# mother_card_15.net
KiCad netlist of a schematic drawn in EAGLE
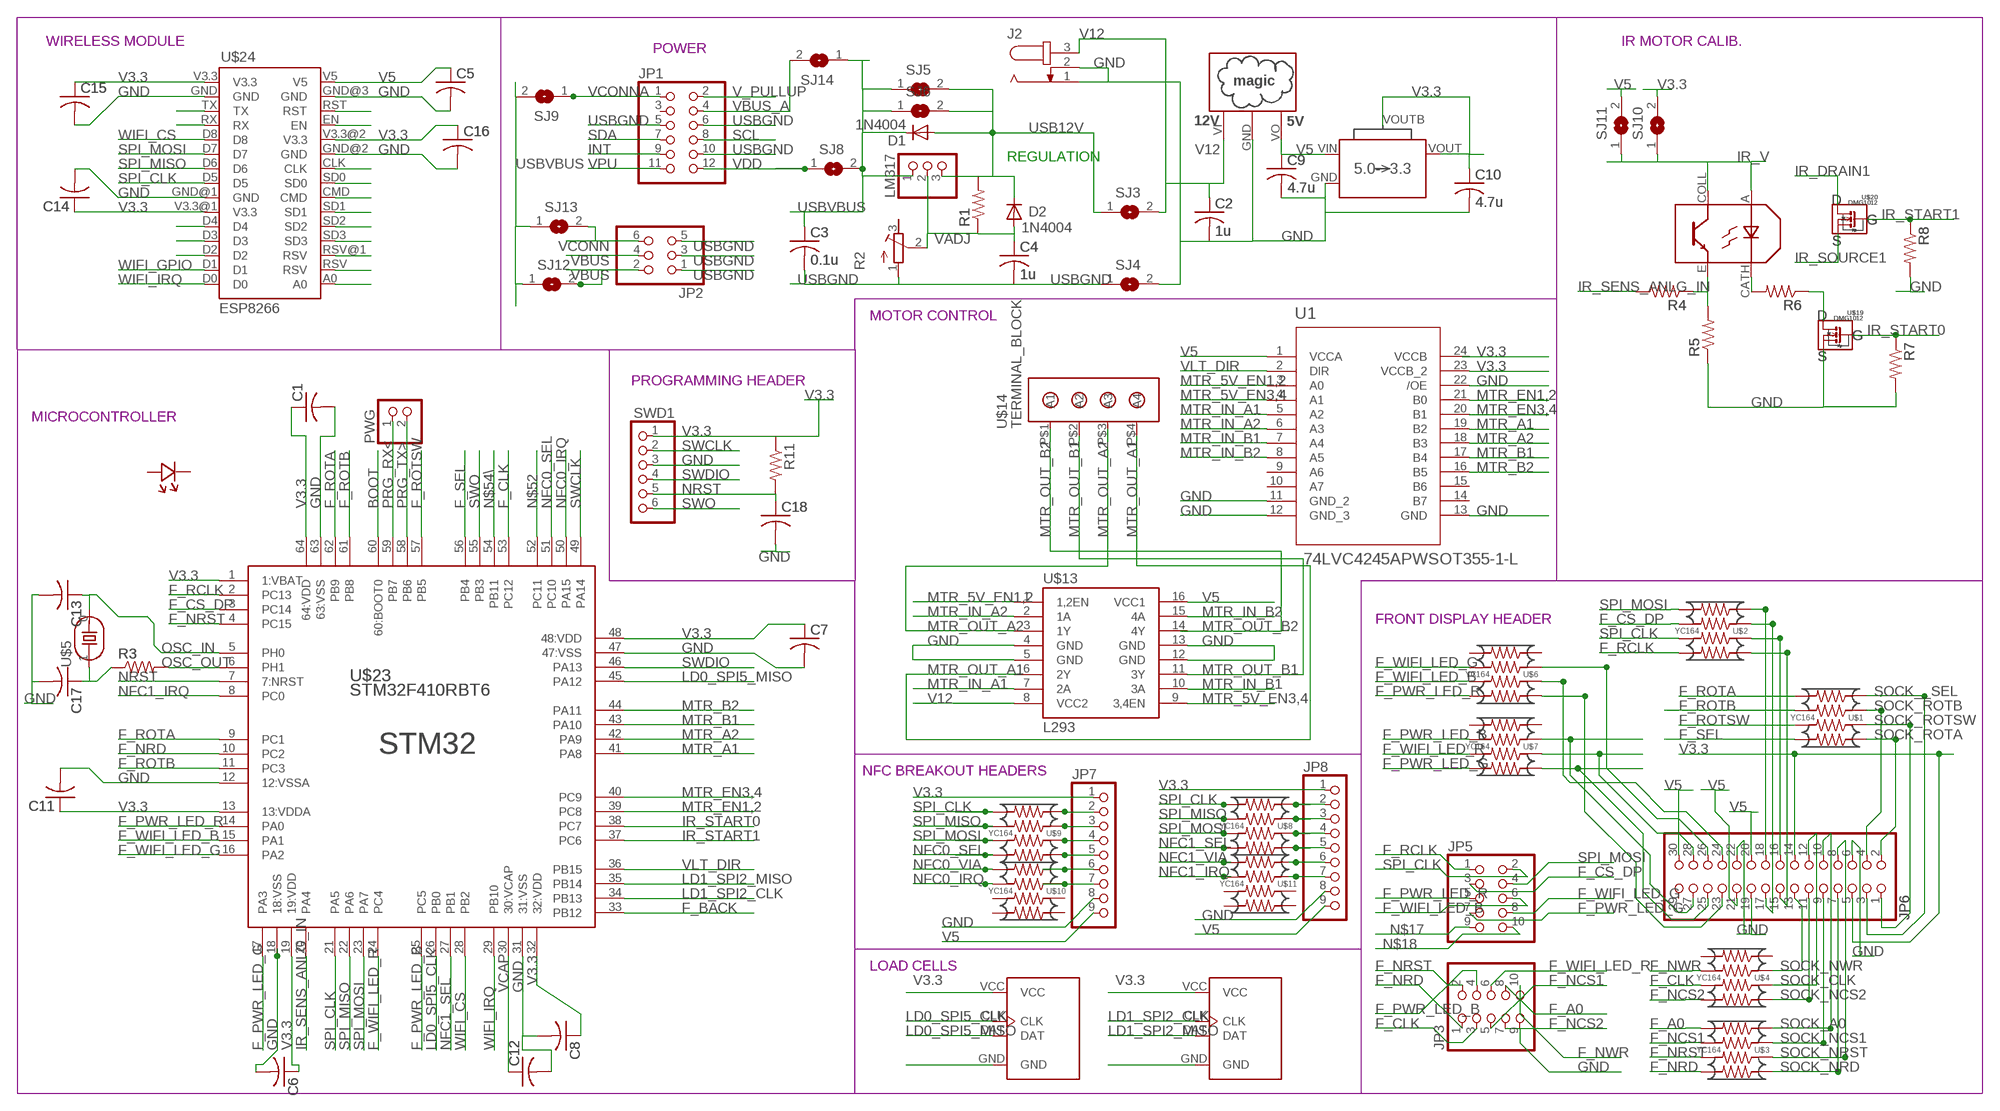
[diagram p0: schematic, sheet 1]

(export (version "E")
  (design (tool "Eeschema 10.0.6"))
  (components
    (comp (ref "C1")
      (value "C-USC0805")
      (footprint "eagle-import:C0805")
      (libsource (lib "eagle-import") (part "C-USC0805"))
    )
    (comp (ref "C2")
      (value "1u")
      (footprint "eagle-import:C0805")
      (libsource (lib "eagle-import") (part "C-USC0805"))
    )
    (comp (ref "C3")
      (value "0.1u")
      (footprint "eagle-import:C0805")
      (libsource (lib "eagle-import") (part "C-USC0805"))
    )
    (comp (ref "C4")
      (value "1u")
      (footprint "eagle-import:C0805")
      (libsource (lib "eagle-import") (part "C-USC0805"))
    )
    (comp (ref "C5")
      (value "C-USC0805")
      (footprint "eagle-import:C0805")
      (libsource (lib "eagle-import") (part "C-USC0805"))
    )
    (comp (ref "C6")
      (value "C-USC0805")
      (footprint "eagle-import:C0805")
      (libsource (lib "eagle-import") (part "C-USC0805"))
    )
    (comp (ref "C7")
      (value "C-USC0805")
      (footprint "eagle-import:C0805")
      (libsource (lib "eagle-import") (part "C-USC0805"))
    )
    (comp (ref "C8")
      (value "C-USC0805")
      (footprint "eagle-import:C0805")
      (libsource (lib "eagle-import") (part "C-USC0805"))
    )
    (comp (ref "C9")
      (value "4.7u")
      (footprint "eagle-import:C0805")
      (libsource (lib "eagle-import") (part "C-USC0805"))
    )
    (comp (ref "C10")
      (value "4.7u")
      (footprint "eagle-import:C0805")
      (libsource (lib "eagle-import") (part "C-USC0805"))
    )
    (comp (ref "C11")
      (value "C-USC0805")
      (footprint "eagle-import:C0805")
      (libsource (lib "eagle-import") (part "C-USC0805"))
    )
    (comp (ref "C12")
      (value "C-USC0805")
      (footprint "eagle-import:C0805")
      (libsource (lib "eagle-import") (part "C-USC0805"))
    )
    (comp (ref "C13")
      (value "C-USC0603")
      (footprint "eagle-import:C0603")
      (libsource (lib "eagle-import") (part "C-USC0603"))
    )
    (comp (ref "C14")
      (value "C-USC0805")
      (footprint "eagle-import:C0805")
      (libsource (lib "eagle-import") (part "C-USC0805"))
    )
    (comp (ref "C15")
      (value "C-USC0805")
      (footprint "eagle-import:C0805")
      (libsource (lib "eagle-import") (part "C-USC0805"))
    )
    (comp (ref "C16")
      (value "C-USC0805")
      (footprint "eagle-import:C0805")
      (libsource (lib "eagle-import") (part "C-USC0805"))
    )
    (comp (ref "C17")
      (value "C-USC0603")
      (footprint "eagle-import:C0603")
      (libsource (lib "eagle-import") (part "C-USC0603"))
    )
    (comp (ref "C18")
      (value "C-USC0805")
      (footprint "eagle-import:C0805")
      (libsource (lib "eagle-import") (part "C-USC0805"))
    )
    (comp (ref "D1")
      (value "1N4004")
      (footprint "eagle-import:DO41-10")
      (libsource (lib "eagle-import") (part "1N4004"))
    )
    (comp (ref "D2")
      (value "1N4004")
      (footprint "eagle-import:DO41-10")
      (libsource (lib "eagle-import") (part "1N4004"))
    )
    (comp (ref "J2")
      (value "JACK-PLUG0")
      (footprint "eagle-import:SPC4077")
      (libsource (lib "eagle-import") (part "JACK-PLUG0"))
    )
    (comp (ref "JP1")
      (value "PINHD-2X6")
      (footprint "eagle-import:2X06")
      (libsource (lib "eagle-import") (part "PINHD-2X6"))
    )
    (comp (ref "JP2")
      (value "PINHD-2X3")
      (footprint "eagle-import:2X03")
      (libsource (lib "eagle-import") (part "PINHD-2X3"))
    )
    (comp (ref "JP3")
      (value "PINHD-2X5")
      (footprint "eagle-import:2X05")
      (libsource (lib "eagle-import") (part "PINHD-2X5"))
    )
    (comp (ref "JP5")
      (value "PINHD-2X5")
      (footprint "eagle-import:2X05")
      (libsource (lib "eagle-import") (part "PINHD-2X5"))
    )
    (comp (ref "JP6")
      (value "PINHD-2X15/SOCK")
      (footprint "eagle-import:2X15_SOCK")
      (libsource (lib "eagle-import") (part "PINHD-2X15/SOCK"))
    )
    (comp (ref "JP7")
      (value "PINHD-1X9/90")
      (footprint "eagle-import:1X09_90")
      (libsource (lib "eagle-import") (part "PINHD-1X9/90"))
    )
    (comp (ref "JP8")
      (value "PINHD-1X9/90")
      (footprint "eagle-import:1X09_90")
      (libsource (lib "eagle-import") (part "PINHD-1X9/90"))
    )
    (comp (ref "LM317")
      (value "PINHD-1X3")
      (footprint "eagle-import:1X03")
      (libsource (lib "eagle-import") (part "PINHD-1X3"))
    )
    (comp (ref "PWG")
      (value "PINHD-1X2")
      (footprint "eagle-import:1X02")
      (libsource (lib "eagle-import") (part "PINHD-1X2"))
    )
    (comp (ref "R1")
      (value "R-US_R0805")
      (footprint "eagle-import:R0805")
      (libsource (lib "eagle-import") (part "seniorDesign_R-US_R0805"))
    )
    (comp (ref "R2")
      (value "R-TRIMM64W")
      (footprint "eagle-import:RTRIM64W")
      (libsource (lib "eagle-import") (part "R-TRIMM64W"))
    )
    (comp (ref "R3")
      (value "R-US_R0805")
      (footprint "eagle-import:R0805")
      (libsource (lib "eagle-import") (part "seniorDesign_R-US_R0805"))
    )
    (comp (ref "R4")
      (value "R-US_R0805")
      (footprint "eagle-import:R0805")
      (libsource (lib "eagle-import") (part "seniorDesign_R-US_R0805"))
    )
    (comp (ref "R5")
      (value "R-US_R0805")
      (footprint "eagle-import:R0805")
      (libsource (lib "eagle-import") (part "seniorDesign_R-US_R0805"))
    )
    (comp (ref "R6")
      (value "R-US_R0805")
      (footprint "eagle-import:R0805")
      (libsource (lib "eagle-import") (part "seniorDesign_R-US_R0805"))
    )
    (comp (ref "R7")
      (value "R-US_R0805")
      (footprint "eagle-import:R0805")
      (libsource (lib "eagle-import") (part "seniorDesign_R-US_R0805"))
    )
    (comp (ref "R8")
      (value "R-US_R0805")
      (footprint "eagle-import:R0805")
      (libsource (lib "eagle-import") (part "seniorDesign_R-US_R0805"))
    )
    (comp (ref "R11")
      (value "R-US_R0805")
      (footprint "eagle-import:R0805")
      (libsource (lib "eagle-import") (part "R-US_R0805"))
    )
    (comp (ref "SJ3") (value "SJ") (footprint "eagle-import:SJ") (libsource (lib "eagle-import") (part "SJ")))
    (comp (ref "SJ4") (value "SJ") (footprint "eagle-import:SJ") (libsource (lib "eagle-import") (part "SJ")))
    (comp (ref "SJ5") (value "SJ") (footprint "eagle-import:SJ") (libsource (lib "eagle-import") (part "SJ")))
    (comp (ref "SJ6") (value "SJ") (footprint "eagle-import:SJ") (libsource (lib "eagle-import") (part "SJ")))
    (comp (ref "SJ8") (value "SJ") (footprint "eagle-import:SJ") (libsource (lib "eagle-import") (part "SJ")))
    (comp (ref "SJ9") (value "SJ") (footprint "eagle-import:SJ") (libsource (lib "eagle-import") (part "SJ")))
    (comp (ref "SJ10")
      (value "SJ")
      (footprint "eagle-import:SJ")
      (libsource (lib "eagle-import") (part "SJ"))
    )
    (comp (ref "SJ11")
      (value "SJ")
      (footprint "eagle-import:SJ")
      (libsource (lib "eagle-import") (part "SJ"))
    )
    (comp (ref "SJ12")
      (value "SJ")
      (footprint "eagle-import:SJ")
      (libsource (lib "eagle-import") (part "SJ"))
    )
    (comp (ref "SJ13")
      (value "SJ")
      (footprint "eagle-import:SJ")
      (libsource (lib "eagle-import") (part "SJ"))
    )
    (comp (ref "SJ14")
      (value "SJ")
      (footprint "eagle-import:SJ")
      (libsource (lib "eagle-import") (part "SJ"))
    )
    (comp (ref "SWD1")
      (value "PINHD-1X6")
      (footprint "eagle-import:1X06")
      (libsource (lib "eagle-import") (part "PINHD-1X6"))
    )
    (comp (ref "U$1")
      (value "YC164")
      (footprint "eagle-import:YC164")
      (libsource (lib "eagle-import") (part "YC164"))
    )
    (comp (ref "U$2")
      (value "YC164")
      (footprint "eagle-import:YC164")
      (libsource (lib "eagle-import") (part "YC164"))
    )
    (comp (ref "U$3")
      (value "YC164")
      (footprint "eagle-import:YC164")
      (libsource (lib "eagle-import") (part "YC164"))
    )
    (comp (ref "U$4")
      (value "YC164")
      (footprint "eagle-import:YC164")
      (libsource (lib "eagle-import") (part "YC164"))
    )
    (comp (ref "U$5")
      (value "HC-49S_9B")
      (footprint "eagle-import:HC-49S_9B")
      (libsource (lib "eagle-import") (part "HC-49S_9B"))
    )
    (comp (ref "U$6")
      (value "YC164")
      (footprint "eagle-import:YC164")
      (libsource (lib "eagle-import") (part "YC164"))
    )
    (comp (ref "U$7")
      (value "YC164")
      (footprint "eagle-import:YC164")
      (libsource (lib "eagle-import") (part "YC164"))
    )
    (comp (ref "U$8")
      (value "YC164")
      (footprint "eagle-import:YC164")
      (libsource (lib "eagle-import") (part "YC164"))
    )
    (comp (ref "U$9")
      (value "YC164")
      (footprint "eagle-import:YC164")
      (libsource (lib "eagle-import") (part "YC164"))
    )
    (comp (ref "U$10")
      (value "YC164")
      (footprint "eagle-import:YC164")
      (libsource (lib "eagle-import") (part "YC164"))
    )
    (comp (ref "U$11")
      (value "YC164")
      (footprint "eagle-import:YC164")
      (libsource (lib "eagle-import") (part "YC164"))
    )
    (comp (ref "U$12")
      (value "LED0603")
      (footprint "eagle-import:LED")
      (libsource (lib "eagle-import") (part "LED0603"))
    )
    (comp (ref "U$13")
      (value "L293")
      (footprint "eagle-import:DIL16")
      (libsource (lib "eagle-import") (part "L293"))
    )
    (comp (ref "U$14")
      (value "TERMINAL_BLOCK")
      (footprint "eagle-import:1X4_BLOCK")
      (libsource (lib "eagle-import") (part "TERMINAL_BLOCK"))
    )
    (comp (ref "U$15")
      (value "AP2114H")
      (footprint "eagle-import:AP2114H")
      (libsource (lib "eagle-import") (part "AP2114H"))
    )
    (comp (ref "U$16")
      (value "OKI-78SR-W36")
      (footprint "eagle-import:SIP3")
      (libsource (lib "eagle-import") (part "OKI-78SR-W36"))
    )
    (comp (ref "U$18")
      (value "TCRT5000")
      (footprint "eagle-import:TCRT5000")
      (libsource (lib "eagle-import") (part "TCRT5000"))
    )
    (comp (ref "U$19")
      (value "DMG1012")
      (footprint "eagle-import:SOT323")
      (libsource (lib "eagle-import") (part "DMG1012"))
    )
    (comp (ref "U$20")
      (value "DMG1012")
      (footprint "eagle-import:SOT323")
      (libsource (lib "eagle-import") (part "DMG1012"))
    )
    (comp (ref "U$21")
      (value "HX711")
      (footprint "eagle-import:HX711")
      (libsource (lib "eagle-import") (part "HX711"))
    )
    (comp (ref "U$22")
      (value "HX711")
      (footprint "eagle-import:HX711")
      (libsource (lib "eagle-import") (part "HX711"))
    )
    (comp (ref "U$23")
      (value "STM32F410RBT6")
      (footprint "eagle-import:QFP50P1200X1200X160-64N")
      (libsource (lib "eagle-import") (part "STM32F410RBT6"))
    )
    (comp (ref "U$24")
      (value "ESP8266")
      (footprint "eagle-import:ESP8266")
      (libsource (lib "eagle-import") (part "ESP8266"))
    )
    (comp (ref "U1")
      (value "74LVC4245APWSOT355-1-L")
      (footprint "eagle-import:SOT355-1-L")
      (fields (field (name "MANUFACTURER_PART_NUMBER") "74LVC4245APW"))
      (libsource (lib "eagle-import") (part "74LVC4245APWSOT355-1-L"))
    )
  )
  (nets
    (net (code "1") (name "/BOOT") (class "Default")
      (node (ref "U$23") (pin "60") (pinfunction "60:BOOT0_60") (pintype "bidirectional"))
    )
    (net (code "2") (name "/F_A0") (class "Default")
      (node (ref "JP3") (pin "8") (pinfunction "8_8") (pintype "passive"))
      (node (ref "U$3") (pin "P$4") (pinfunction "4_P$4") (pintype "passive"))
    )
    (net (code "3") (name "/F_BACK") (class "Default")
      (node (ref "U$23") (pin "33") (pinfunction "PB12_33") (pintype "bidirectional"))
    )
    (net (code "4") (name "/F_CLK") (class "Default")
      (node (ref "JP3") (pin "3") (pinfunction "3_3") (pintype "passive"))
      (node (ref "U$23") (pin "53") (pinfunction "PC12_53") (pintype "bidirectional"))
      (node (ref "U$4") (pin "P$2") (pinfunction "2_P$2") (pintype "passive"))
    )
    (net (code "5") (name "/F_CS_DP") (class "Default")
      (node (ref "JP5") (pin "3") (pinfunction "3_3") (pintype "passive"))
      (node (ref "U$2") (pin "P$3") (pinfunction "3_P$3") (pintype "passive"))
      (node (ref "U$23") (pin "3") (pinfunction "PC14_3") (pintype "bidirectional"))
    )
    (net (code "6") (name "/F_NCS1") (class "Default")
      (node (ref "JP3") (pin "5") (pinfunction "5_5") (pintype "passive"))
      (node (ref "U$3") (pin "P$3") (pinfunction "3_P$3") (pintype "passive"))
    )
    (net (code "7") (name "/F_NCS2") (class "Default")
      (node (ref "JP3") (pin "7") (pinfunction "7_7") (pintype "passive"))
      (node (ref "U$4") (pin "P$1") (pinfunction "1_P$1") (pintype "passive"))
    )
    (net (code "8") (name "/F_NRD") (class "Default")
      (node (ref "JP3") (pin "1") (pinfunction "1_1") (pintype "passive"))
      (node (ref "U$23") (pin "10") (pinfunction "PC2_10") (pintype "bidirectional"))
      (node (ref "U$3") (pin "P$1") (pinfunction "1_P$1") (pintype "passive"))
    )
    (net (code "9") (name "/F_NRST") (class "Default")
      (node (ref "JP3") (pin "2") (pinfunction "2_2") (pintype "passive"))
      (node (ref "U$23") (pin "4") (pinfunction "PC15_4") (pintype "bidirectional"))
      (node (ref "U$3") (pin "P$2") (pinfunction "2_P$2") (pintype "passive"))
    )
    (net (code "10") (name "/F_NWR") (class "Default")
      (node (ref "JP3") (pin "10") (pinfunction "10_10") (pintype "passive"))
      (node (ref "U$4") (pin "P$3") (pinfunction "3_P$3") (pintype "passive"))
    )
    (net (code "11") (name "/F_PWR_LED_B") (class "Default")
      (node (ref "JP3") (pin "4") (pinfunction "4_4") (pintype "passive"))
      (node (ref "U$23") (pin "25") (pinfunction "PC5_25") (pintype "bidirectional"))
      (node (ref "U$7") (pin "P$3") (pinfunction "3_P$3") (pintype "passive"))
    )
    (net (code "12") (name "/F_PWR_LED_G") (class "Default")
      (node (ref "JP5") (pin "7") (pinfunction "7_7") (pintype "passive"))
      (node (ref "U$23") (pin "17") (pinfunction "PA3_17") (pintype "bidirectional"))
      (node (ref "U$7") (pin "P$1") (pinfunction "1_P$1") (pintype "passive"))
    )
    (net (code "13") (name "/F_PWR_LED_R") (class "Default")
      (node (ref "JP5") (pin "5") (pinfunction "5_5") (pintype "passive"))
      (node (ref "U$23") (pin "14") (pinfunction "PA0_14") (pintype "bidirectional"))
      (node (ref "U$6") (pin "P$1") (pinfunction "1_P$1") (pintype "passive"))
    )
    (net (code "14") (name "/F_RCLK") (class "Default")
      (node (ref "JP5") (pin "1") (pinfunction "1_1") (pintype "passive"))
      (node (ref "U$2") (pin "P$1") (pinfunction "1_P$1") (pintype "passive"))
      (node (ref "U$23") (pin "2") (pinfunction "PC13_2") (pintype "bidirectional"))
    )
    (net (code "15") (name "/F_ROTA") (class "Default")
      (node (ref "U$1") (pin "P$4") (pinfunction "4_P$4") (pintype "passive"))
      (node (ref "U$23") (pin "62") (pinfunction "PB9_62") (pintype "bidirectional"))
      (node (ref "U$23") (pin "9") (pinfunction "PC1_9") (pintype "bidirectional"))
    )
    (net (code "16") (name "/F_ROTB") (class "Default")
      (node (ref "U$1") (pin "P$3") (pinfunction "3_P$3") (pintype "passive"))
      (node (ref "U$23") (pin "11") (pinfunction "PC3_11") (pintype "bidirectional"))
      (node (ref "U$23") (pin "61") (pinfunction "PB8_61") (pintype "bidirectional"))
    )
    (net (code "17") (name "/F_ROTSW") (class "Default")
      (node (ref "U$1") (pin "P$2") (pinfunction "2_P$2") (pintype "passive"))
      (node (ref "U$23") (pin "57") (pinfunction "PB5_57") (pintype "bidirectional"))
    )
    (net (code "18") (name "/F_SEL") (class "Default")
      (node (ref "U$1") (pin "P$1") (pinfunction "1_P$1") (pintype "passive"))
      (node (ref "U$23") (pin "56") (pinfunction "PB4_56") (pintype "bidirectional"))
    )
    (net (code "19") (name "/F_WIFI_LED_B") (class "Default")
      (node (ref "JP5") (pin "6") (pinfunction "6_6") (pintype "passive"))
      (node (ref "U$23") (pin "15") (pinfunction "PA1_15") (pintype "bidirectional"))
      (node (ref "U$6") (pin "P$2") (pinfunction "2_P$2") (pintype "passive"))
    )
    (net (code "20") (name "/F_WIFI_LED_G") (class "Default")
      (node (ref "JP5") (pin "8") (pinfunction "8_8") (pintype "passive"))
      (node (ref "U$23") (pin "16") (pinfunction "PA2_16") (pintype "bidirectional"))
      (node (ref "U$6") (pin "P$3") (pinfunction "3_P$3") (pintype "passive"))
    )
    (net (code "21") (name "/F_WIFI_LED_R") (class "Default")
      (node (ref "JP3") (pin "6") (pinfunction "6_6") (pintype "passive"))
      (node (ref "U$23") (pin "24") (pinfunction "PC4_24") (pintype "bidirectional"))
      (node (ref "U$7") (pin "P$2") (pinfunction "2_P$2") (pintype "passive"))
    )
    (net (code "22") (name "/GND") (class "Default")
      (node (ref "C1") (pin "2") (pinfunction "2_2") (pintype "passive"))
      (node (ref "C10") (pin "2") (pinfunction "2_2") (pintype "passive"))
      (node (ref "C11") (pin "2") (pinfunction "2_2") (pintype "passive"))
      (node (ref "C12") (pin "2") (pinfunction "2_2") (pintype "passive"))
      (node (ref "C13") (pin "2") (pinfunction "2_2") (pintype "passive"))
      (node (ref "C14") (pin "2") (pinfunction "2_2") (pintype "passive"))
      (node (ref "C15") (pin "2") (pinfunction "2_2") (pintype "passive"))
      (node (ref "C16") (pin "2") (pinfunction "2_2") (pintype "passive"))
      (node (ref "C17") (pin "2") (pinfunction "2_2") (pintype "passive"))
      (node (ref "C18") (pin "2") (pinfunction "2_2") (pintype "passive"))
      (node (ref "C2") (pin "2") (pinfunction "2_2") (pintype "passive"))
      (node (ref "C5") (pin "2") (pinfunction "2_2") (pintype "passive"))
      (node (ref "C6") (pin "2") (pinfunction "2_2") (pintype "passive"))
      (node (ref "C7") (pin "2") (pinfunction "2_2") (pintype "passive"))
      (node (ref "C8") (pin "2") (pinfunction "2_2") (pintype "passive"))
      (node (ref "C9") (pin "2") (pinfunction "2_2") (pintype "passive"))
      (node (ref "J2") (pin "1") (pinfunction "1_1") (pintype "passive"))
      (node (ref "J2") (pin "2") (pinfunction "2_2") (pintype "passive"))
      (node (ref "JP3") (pin "9") (pinfunction "9_9") (pintype "passive"))
      (node (ref "JP6") (pin "19") (pinfunction "19_19") (pintype "passive"))
      (node (ref "JP6") (pin "22") (pinfunction "22_22") (pintype "passive"))
      (node (ref "JP6") (pin "6") (pinfunction "6_6") (pintype "passive"))
      (node (ref "JP7") (pin "8") (pinfunction "8_8") (pintype "passive"))
      (node (ref "JP8") (pin "8") (pinfunction "8_8") (pintype "passive"))
      (node (ref "R5") (pin "1") (pinfunction "1_1") (pintype "passive"))
      (node (ref "R7") (pin "2") (pinfunction "2_2") (pintype "passive"))
      (node (ref "R8") (pin "2") (pinfunction "2_2") (pintype "passive"))
      (node (ref "SJ4") (pin "2") (pinfunction "2_2") (pintype "passive"))
      (node (ref "SWD1") (pin "3") (pinfunction "3_3") (pintype "passive"))
      (node (ref "U$13") (pin "12") (pinfunction "GND_12") (pintype "bidirectional"))
      (node (ref "U$13") (pin "13") (pinfunction "GND_13") (pintype "bidirectional"))
      (node (ref "U$13") (pin "4") (pinfunction "GND_4") (pintype "bidirectional"))
      (node (ref "U$13") (pin "5") (pinfunction "GND_5") (pintype "bidirectional"))
      (node (ref "U$15") (pin "GND") (pinfunction "GND_GND") (pintype "power_in"))
      (node (ref "U$16") (pin "GND") (pinfunction "P$2_GND") (pintype "power_in"))
      (node (ref "U$19") (pin "S") (pinfunction "S_S") (pintype "bidirectional"))
      (node (ref "U$21") (pin "GND") (pinfunction "GND_GND") (pintype "power_in"))
      (node (ref "U$22") (pin "GND") (pinfunction "GND_GND") (pintype "power_in"))
      (node (ref "U$23") (pin "12") (pinfunction "12:VSSA_12") (pintype "bidirectional"))
      (node (ref "U$23") (pin "18") (pinfunction "18:VSS_18") (pintype "bidirectional"))
      (node (ref "U$23") (pin "31") (pinfunction "31:VSS_31") (pintype "bidirectional"))
      (node (ref "U$23") (pin "47") (pinfunction "47:VSS_47") (pintype "bidirectional"))
      (node (ref "U$23") (pin "63") (pinfunction "63:VSS_63") (pintype "bidirectional"))
      (node (ref "U$24") (pin "GND") (pinfunction "GND_GND") (pintype "bidirectional"))
      (node (ref "U$24") (pin "GND@1") (pinfunction "GND_GND@1") (pintype "bidirectional"))
      (node (ref "U$24") (pin "GND@2") (pinfunction "GND_GND@2") (pintype "bidirectional"))
      (node (ref "U$24") (pin "GND@3") (pinfunction "GND_GND@3") (pintype "bidirectional"))
      (node (ref "U1") (pin "11") (pinfunction "GND_2_11") (pintype "power_in"))
      (node (ref "U1") (pin "12") (pinfunction "GND_3_12") (pintype "power_in"))
      (node (ref "U1") (pin "13") (pinfunction "GND_13") (pintype "power_in"))
      (node (ref "U1") (pin "22") (pinfunction "/OE_22") (pintype "input"))
    )
    (net (code "23") (name "/INT") (class "Default")
      (node (ref "JP1") (pin "9") (pinfunction "9_9") (pintype "passive"))
    )
    (net (code "24") (name "/IR_DRAIN1") (class "Default")
      (node (ref "U$20") (pin "D") (pinfunction "D_D") (pintype "bidirectional"))
    )
    (net (code "25") (name "/IR_SENS_ANLG_IN") (class "Default")
      (node (ref "R4") (pin "2") (pinfunction "2_2") (pintype "passive"))
      (node (ref "U$23") (pin "20") (pinfunction "PA4_20") (pintype "bidirectional"))
    )
    (net (code "26") (name "/IR_SOURCE1") (class "Default")
      (node (ref "U$20") (pin "S") (pinfunction "S_S") (pintype "bidirectional"))
    )
    (net (code "27") (name "/IR_START0") (class "Default")
      (node (ref "R7") (pin "1") (pinfunction "1_1") (pintype "passive"))
      (node (ref "U$19") (pin "G") (pinfunction "G_G") (pintype "bidirectional"))
      (node (ref "U$23") (pin "38") (pinfunction "PC7_38") (pintype "bidirectional"))
    )
    (net (code "28") (name "/IR_START1") (class "Default")
      (node (ref "R8") (pin "1") (pinfunction "1_1") (pintype "passive"))
      (node (ref "U$20") (pin "G") (pinfunction "G_G") (pintype "bidirectional"))
      (node (ref "U$23") (pin "37") (pinfunction "PC6_37") (pintype "bidirectional"))
    )
    (net (code "29") (name "/IR_V") (class "Default")
      (node (ref "SJ10") (pin "1") (pinfunction "1_1") (pintype "passive"))
      (node (ref "SJ11") (pin "1") (pinfunction "1_1") (pintype "passive"))
      (node (ref "U$18") (pin "A") (pinfunction "A_A") (pintype "bidirectional"))
      (node (ref "U$18") (pin "COLL") (pinfunction "COLL_COLL") (pintype "bidirectional"))
    )
    (net (code "30") (name "/LD0_SPI5_CLK") (class "Default")
      (node (ref "U$21") (pin "CLK") (pinfunction "CLK_CLK") (pintype "bidirectional"))
      (node (ref "U$23") (pin "26") (pinfunction "PB0_26") (pintype "bidirectional"))
    )
    (net (code "31") (name "/LD0_SPI5_MISO") (class "Default")
      (node (ref "U$21") (pin "DAT") (pinfunction "DAT_DAT") (pintype "bidirectional"))
      (node (ref "U$23") (pin "45") (pinfunction "PA12_45") (pintype "bidirectional"))
    )
    (net (code "32") (name "/LD1_SPI2_CLK") (class "Default")
      (node (ref "U$22") (pin "CLK") (pinfunction "CLK_CLK") (pintype "bidirectional"))
      (node (ref "U$23") (pin "34") (pinfunction "PB13_34") (pintype "bidirectional"))
    )
    (net (code "33") (name "/LD1_SPI2_MISO") (class "Default")
      (node (ref "U$22") (pin "DAT") (pinfunction "DAT_DAT") (pintype "bidirectional"))
      (node (ref "U$23") (pin "35") (pinfunction "PB14_35") (pintype "bidirectional"))
    )
    (net (code "34") (name "/MTR_5V_EN1,2") (class "Default")
      (node (ref "U$13") (pin "1") (pinfunction "1,2EN_1") (pintype "bidirectional"))
      (node (ref "U1") (pin "3") (pinfunction "A0_3") (pintype "bidirectional"))
    )
    (net (code "35") (name "/MTR_5V_EN3,4") (class "Default")
      (node (ref "U$13") (pin "9") (pinfunction "3,4EN_9") (pintype "bidirectional"))
      (node (ref "U1") (pin "4") (pinfunction "A1_4") (pintype "bidirectional"))
    )
    (net (code "36") (name "/MTR_A1") (class "Default")
      (node (ref "U$23") (pin "41") (pinfunction "PA8_41") (pintype "bidirectional"))
      (node (ref "U1") (pin "19") (pinfunction "B2_19") (pintype "bidirectional"))
    )
    (net (code "37") (name "/MTR_A2") (class "Default")
      (node (ref "U$23") (pin "42") (pinfunction "PA9_42") (pintype "bidirectional"))
      (node (ref "U1") (pin "18") (pinfunction "B3_18") (pintype "bidirectional"))
    )
    (net (code "38") (name "/MTR_B1") (class "Default")
      (node (ref "U$23") (pin "43") (pinfunction "PA10_43") (pintype "bidirectional"))
      (node (ref "U1") (pin "17") (pinfunction "B4_17") (pintype "bidirectional"))
    )
    (net (code "39") (name "/MTR_B2") (class "Default")
      (node (ref "U$23") (pin "44") (pinfunction "PA11_44") (pintype "bidirectional"))
      (node (ref "U1") (pin "16") (pinfunction "B5_16") (pintype "bidirectional"))
    )
    (net (code "40") (name "/MTR_EN1,2") (class "Default")
      (node (ref "U$23") (pin "39") (pinfunction "PC8_39") (pintype "bidirectional"))
      (node (ref "U1") (pin "21") (pinfunction "B0_21") (pintype "bidirectional"))
    )
    (net (code "41") (name "/MTR_EN3,4") (class "Default")
      (node (ref "U$23") (pin "40") (pinfunction "PC9_40") (pintype "bidirectional"))
      (node (ref "U1") (pin "20") (pinfunction "B1_20") (pintype "bidirectional"))
    )
    (net (code "42") (name "/MTR_IN_A1") (class "Default")
      (node (ref "U$13") (pin "7") (pinfunction "2A_7") (pintype "bidirectional"))
      (node (ref "U1") (pin "5") (pinfunction "A2_5") (pintype "bidirectional"))
    )
    (net (code "43") (name "/MTR_IN_A2") (class "Default")
      (node (ref "U$13") (pin "2") (pinfunction "1A_2") (pintype "bidirectional"))
      (node (ref "U1") (pin "6") (pinfunction "A3_6") (pintype "bidirectional"))
    )
    (net (code "44") (name "/MTR_IN_B1") (class "Default")
      (node (ref "U$13") (pin "10") (pinfunction "3A_10") (pintype "bidirectional"))
      (node (ref "U1") (pin "7") (pinfunction "A4_7") (pintype "bidirectional"))
    )
    (net (code "45") (name "/MTR_IN_B2") (class "Default")
      (node (ref "U$13") (pin "15") (pinfunction "4A_15") (pintype "bidirectional"))
      (node (ref "U1") (pin "8") (pinfunction "A5_8") (pintype "bidirectional"))
    )
    (net (code "46") (name "/MTR_OUT_A1") (class "Default")
      (node (ref "U$13") (pin "6") (pinfunction "2Y_6") (pintype "bidirectional"))
      (node (ref "U$14") (pin "P$4") (pinfunction "A4_P$4") (pintype "bidirectional"))
    )
    (net (code "47") (name "/MTR_OUT_A2") (class "Default")
      (node (ref "U$13") (pin "3") (pinfunction "1Y_3") (pintype "bidirectional"))
      (node (ref "U$14") (pin "P$3") (pinfunction "A3_P$3") (pintype "bidirectional"))
    )
    (net (code "48") (name "/MTR_OUT_B1") (class "Default")
      (node (ref "U$13") (pin "11") (pinfunction "3Y_11") (pintype "bidirectional"))
      (node (ref "U$14") (pin "P$2") (pinfunction "A2_P$2") (pintype "bidirectional"))
    )
    (net (code "49") (name "/MTR_OUT_B2") (class "Default")
      (node (ref "U$13") (pin "14") (pinfunction "4Y_14") (pintype "bidirectional"))
      (node (ref "U$14") (pin "P$1") (pinfunction "A1_P$1") (pintype "bidirectional"))
    )
    (net (code "50") (name "/N$17") (class "Default")
      (node (ref "JP5") (pin "9") (pinfunction "9_9") (pintype "passive"))
    )
    (net (code "51") (name "/N$18") (class "Default")
      (node (ref "JP5") (pin "10") (pinfunction "10_10") (pintype "passive"))
    )
    (net (code "52") (name "/N$52") (class "Default")
      (node (ref "U$23") (pin "52") (pinfunction "PC11_52") (pintype "bidirectional"))
    )
    (net (code "53") (name "/N$54\\") (class "Default")
      (node (ref "U$23") (pin "54") (pinfunction "PB11_54") (pintype "bidirectional"))
    )
    (net (code "54") (name "/NFC0_IRQ") (class "Default")
      (node (ref "U$10") (pin "P$3") (pinfunction "3_P$3") (pintype "passive"))
      (node (ref "U$23") (pin "50") (pinfunction "PA15_50") (pintype "bidirectional"))
    )
    (net (code "55") (name "/NFC0_SEL") (class "Default")
      (node (ref "U$23") (pin "51") (pinfunction "PC10_51") (pintype "bidirectional"))
      (node (ref "U$9") (pin "P$1") (pinfunction "1_P$1") (pintype "passive"))
    )
    (net (code "56") (name "/NFC0_VIA") (class "Default")
      (node (ref "U$10") (pin "P$4") (pinfunction "4_P$4") (pintype "passive"))
    )
    (net (code "57") (name "/NFC1_IRQ") (class "Default")
      (node (ref "U$11") (pin "P$3") (pinfunction "3_P$3") (pintype "passive"))
      (node (ref "U$23") (pin "8") (pinfunction "PC0_8") (pintype "bidirectional"))
    )
    (net (code "58") (name "/NFC1_SEL") (class "Default")
      (node (ref "U$23") (pin "27") (pinfunction "PB1_27") (pintype "bidirectional"))
      (node (ref "U$8") (pin "P$1") (pinfunction "1_P$1") (pintype "passive"))
    )
    (net (code "59") (name "/NFC1_VIA") (class "Default")
      (node (ref "U$11") (pin "P$4") (pinfunction "4_P$4") (pintype "passive"))
    )
    (net (code "60") (name "/NRST") (class "Default")
      (node (ref "C18") (pin "1") (pinfunction "1_1") (pintype "passive"))
      (node (ref "R11") (pin "2") (pinfunction "2_2") (pintype "passive"))
      (node (ref "SWD1") (pin "5") (pinfunction "5_5") (pintype "passive"))
      (node (ref "U$23") (pin "7") (pinfunction "7:NRST_7") (pintype "bidirectional"))
    )
    (net (code "61") (name "/OSC_IN") (class "Default")
      (node (ref "C13") (pin "1") (pinfunction "1_1") (pintype "passive"))
      (node (ref "U$23") (pin "5") (pinfunction "PH0_5") (pintype "bidirectional"))
      (node (ref "U$5") (pin "0") (pinfunction "P$1_0") (pintype "bidirectional"))
    )
    (net (code "62") (name "/OSC_OUT") (class "Default")
      (node (ref "C17") (pin "1") (pinfunction "1_1") (pintype "passive"))
      (node (ref "R3") (pin "1") (pinfunction "1_1") (pintype "passive"))
      (node (ref "U$5") (pin "1") (pinfunction "P$2_1") (pintype "bidirectional"))
    )
    (net (code "63") (name "/PRG_RX<") (class "Default")
      (node (ref "PWG") (pin "1") (pinfunction "1_1") (pintype "passive"))
      (node (ref "U$23") (pin "59") (pinfunction "PB7_59") (pintype "bidirectional"))
    )
    (net (code "64") (name "/PRG_TX>") (class "Default")
      (node (ref "PWG") (pin "2") (pinfunction "2_2") (pintype "passive"))
      (node (ref "U$23") (pin "58") (pinfunction "PB6_58") (pintype "bidirectional"))
    )
    (net (code "65") (name "/SCL") (class "Default")
      (node (ref "JP1") (pin "8") (pinfunction "8_8") (pintype "passive"))
    )
    (net (code "66") (name "/SDA") (class "Default")
      (node (ref "JP1") (pin "7") (pinfunction "7_7") (pintype "passive"))
    )
    (net (code "67") (name "/SOCK_A0") (class "Default")
      (node (ref "JP6") (pin "10") (pinfunction "10_10") (pintype "passive"))
      (node (ref "U$3") (pin "P$44") (pinfunction "44_P$44") (pintype "passive"))
    )
    (net (code "68") (name "/SOCK_CLK") (class "Default")
      (node (ref "JP6") (pin "12") (pinfunction "12_12") (pintype "passive"))
      (node (ref "U$4") (pin "P$22") (pinfunction "22_P$22") (pintype "passive"))
    )
    (net (code "69") (name "/SOCK_NCS1") (class "Default")
      (node (ref "JP6") (pin "9") (pinfunction "9_9") (pintype "passive"))
      (node (ref "U$3") (pin "P$33") (pinfunction "33_P$33") (pintype "passive"))
    )
    (net (code "70") (name "/SOCK_NCS2") (class "Default")
      (node (ref "JP6") (pin "11") (pinfunction "11_11") (pintype "passive"))
      (node (ref "U$4") (pin "P$11") (pinfunction "11_P$11") (pintype "passive"))
    )
    (net (code "71") (name "/SOCK_NRD") (class "Default")
      (node (ref "JP6") (pin "7") (pinfunction "7_7") (pintype "passive"))
      (node (ref "U$3") (pin "P$11") (pinfunction "11_P$11") (pintype "passive"))
    )
    (net (code "72") (name "/SOCK_NRST") (class "Default")
      (node (ref "JP6") (pin "8") (pinfunction "8_8") (pintype "passive"))
      (node (ref "U$3") (pin "P$22") (pinfunction "22_P$22") (pintype "passive"))
    )
    (net (code "73") (name "/SOCK_NWR") (class "Default")
      (node (ref "JP6") (pin "13") (pinfunction "13_13") (pintype "passive"))
      (node (ref "U$4") (pin "P$33") (pinfunction "33_P$33") (pintype "passive"))
    )
    (net (code "74") (name "/SOCK_ROTA") (class "Default")
      (node (ref "JP6") (pin "2") (pinfunction "2_2") (pintype "passive"))
      (node (ref "U$1") (pin "P$11") (pinfunction "11_P$11") (pintype "passive"))
    )
    (net (code "75") (name "/SOCK_ROTB") (class "Default")
      (node (ref "JP6") (pin "4") (pinfunction "4_4") (pintype "passive"))
      (node (ref "U$1") (pin "P$33") (pinfunction "33_P$33") (pintype "passive"))
    )
    (net (code "76") (name "/SOCK_ROTSW") (class "Default")
      (node (ref "JP6") (pin "1") (pinfunction "1_1") (pintype "passive"))
      (node (ref "U$1") (pin "P$22") (pinfunction "22_P$22") (pintype "passive"))
    )
    (net (code "77") (name "/SOCK__SEL") (class "Default")
      (node (ref "JP6") (pin "3") (pinfunction "3_3") (pintype "passive"))
      (node (ref "U$1") (pin "P$44") (pinfunction "44_P$44") (pintype "passive"))
    )
    (net (code "78") (name "/SPI_CLK") (class "Default")
      (node (ref "JP5") (pin "2") (pinfunction "2_2") (pintype "passive"))
      (node (ref "U$2") (pin "P$2") (pinfunction "2_P$2") (pintype "passive"))
      (node (ref "U$23") (pin "21") (pinfunction "PA5_21") (pintype "bidirectional"))
      (node (ref "U$24") (pin "D5") (pinfunction "D5_D5") (pintype "bidirectional"))
      (node (ref "U$8") (pin "P$4") (pinfunction "4_P$4") (pintype "passive"))
      (node (ref "U$9") (pin "P$4") (pinfunction "4_P$4") (pintype "passive"))
    )
    (net (code "79") (name "/SPI_MISO") (class "Default")
      (node (ref "U$23") (pin "22") (pinfunction "PA6_22") (pintype "bidirectional"))
      (node (ref "U$24") (pin "D6") (pinfunction "D6_D6") (pintype "bidirectional"))
      (node (ref "U$8") (pin "P$3") (pinfunction "3_P$3") (pintype "passive"))
      (node (ref "U$9") (pin "P$3") (pinfunction "3_P$3") (pintype "passive"))
    )
    (net (code "80") (name "/SPI_MOSI") (class "Default")
      (node (ref "JP5") (pin "4") (pinfunction "4_4") (pintype "passive"))
      (node (ref "U$2") (pin "P$4") (pinfunction "4_P$4") (pintype "passive"))
      (node (ref "U$23") (pin "23") (pinfunction "PA7_23") (pintype "bidirectional"))
      (node (ref "U$24") (pin "D7") (pinfunction "D7_D7") (pintype "bidirectional"))
      (node (ref "U$8") (pin "P$2") (pinfunction "2_P$2") (pintype "passive"))
      (node (ref "U$9") (pin "P$2") (pinfunction "2_P$2") (pintype "passive"))
    )
    (net (code "81") (name "/SWCLK") (class "Default")
      (node (ref "SWD1") (pin "2") (pinfunction "2_2") (pintype "passive"))
      (node (ref "U$23") (pin "49") (pinfunction "PA14_49") (pintype "bidirectional"))
    )
    (net (code "82") (name "/SWDIO") (class "Default")
      (node (ref "SWD1") (pin "4") (pinfunction "4_4") (pintype "passive"))
      (node (ref "U$23") (pin "46") (pinfunction "PA13_46") (pintype "bidirectional"))
    )
    (net (code "83") (name "/SWO") (class "Default")
      (node (ref "SWD1") (pin "6") (pinfunction "6_6") (pintype "passive"))
      (node (ref "U$23") (pin "55") (pinfunction "PB3_55") (pintype "bidirectional"))
    )
    (net (code "84") (name "/USB12V") (class "Default")
      (node (ref "D1") (pin "A") (pinfunction "A_A") (pintype "passive"))
      (node (ref "D2") (pin "C") (pinfunction "C_C") (pintype "passive"))
      (node (ref "LM317") (pin "3") (pinfunction "3_3") (pintype "passive"))
      (node (ref "R1") (pin "2") (pinfunction "2_2") (pintype "passive"))
      (node (ref "SJ3") (pin "1") (pinfunction "1_1") (pintype "passive"))
      (node (ref "SJ5") (pin "2") (pinfunction "2_2") (pintype "passive"))
      (node (ref "SJ6") (pin "2") (pinfunction "2_2") (pintype "passive"))
    )
    (net (code "85") (name "/USBGND") (class "Default")
      (node (ref "C3") (pin "2") (pinfunction "2_2") (pintype "passive"))
      (node (ref "C4") (pin "2") (pinfunction "2_2") (pintype "passive"))
      (node (ref "JP1") (pin "10") (pinfunction "10_10") (pintype "passive"))
      (node (ref "JP1") (pin "5") (pinfunction "5_5") (pintype "passive"))
      (node (ref "JP1") (pin "6") (pinfunction "6_6") (pintype "passive"))
      (node (ref "JP2") (pin "1") (pinfunction "1_1") (pintype "passive"))
      (node (ref "JP2") (pin "3") (pinfunction "3_3") (pintype "passive"))
      (node (ref "JP2") (pin "5") (pinfunction "5_5") (pintype "passive"))
      (node (ref "R2") (pin "1") (pinfunction "A_1") (pintype "passive"))
      (node (ref "SJ4") (pin "1") (pinfunction "1_1") (pintype "passive"))
    )
    (net (code "86") (name "/USBVBUS") (class "Default")
      (node (ref "C3") (pin "1") (pinfunction "1_1") (pintype "passive"))
      (node (ref "D1") (pin "C") (pinfunction "C_C") (pintype "passive"))
      (node (ref "LM317") (pin "1") (pinfunction "1_1") (pintype "passive"))
      (node (ref "SJ12") (pin "1") (pinfunction "1_1") (pintype "passive"))
      (node (ref "SJ13") (pin "1") (pinfunction "1_1") (pintype "passive"))
      (node (ref "SJ14") (pin "1") (pinfunction "1_1") (pintype "passive"))
      (node (ref "SJ5") (pin "1") (pinfunction "1_1") (pintype "passive"))
      (node (ref "SJ6") (pin "1") (pinfunction "1_1") (pintype "passive"))
      (node (ref "SJ8") (pin "2") (pinfunction "2_2") (pintype "passive"))
      (node (ref "SJ9") (pin "2") (pinfunction "2_2") (pintype "passive"))
    )
    (net (code "87") (name "/V3.3") (class "Default")
      (node (ref "C1") (pin "1") (pinfunction "1_1") (pintype "passive"))
      (node (ref "C10") (pin "1") (pinfunction "1_1") (pintype "passive"))
      (node (ref "C11") (pin "1") (pinfunction "1_1") (pintype "passive"))
      (node (ref "C14") (pin "1") (pinfunction "1_1") (pintype "passive"))
      (node (ref "C15") (pin "1") (pinfunction "1_1") (pintype "passive"))
      (node (ref "C16") (pin "1") (pinfunction "1_1") (pintype "passive"))
      (node (ref "C6") (pin "1") (pinfunction "1_1") (pintype "passive"))
      (node (ref "C7") (pin "1") (pinfunction "1_1") (pintype "passive"))
      (node (ref "C8") (pin "1") (pinfunction "1_1") (pintype "passive"))
      (node (ref "JP6") (pin "14") (pinfunction "14_14") (pintype "passive"))
      (node (ref "JP6") (pin "5") (pinfunction "5_5") (pintype "passive"))
      (node (ref "JP7") (pin "1") (pinfunction "1_1") (pintype "passive"))
      (node (ref "JP8") (pin "1") (pinfunction "1_1") (pintype "passive"))
      (node (ref "R11") (pin "1") (pinfunction "1_1") (pintype "passive"))
      (node (ref "SJ10") (pin "2") (pinfunction "2_2") (pintype "passive"))
      (node (ref "SWD1") (pin "1") (pinfunction "1_1") (pintype "passive"))
      (node (ref "U$15") (pin "VOUT") (pinfunction "VO_VOUT") (pintype "output"))
      (node (ref "U$15") (pin "VOUTB") (pinfunction "BODY_VOUTB") (pintype "open_collector"))
      (node (ref "U$21") (pin "VCC") (pinfunction "VCC_VCC") (pintype "power_in"))
      (node (ref "U$22") (pin "VCC") (pinfunction "VCC_VCC") (pintype "power_in"))
      (node (ref "U$23") (pin "1") (pinfunction "1:VBAT_1") (pintype "bidirectional"))
      (node (ref "U$23") (pin "13") (pinfunction "13:VDDA_13") (pintype "bidirectional"))
      (node (ref "U$23") (pin "19") (pinfunction "19:VDD_19") (pintype "bidirectional"))
      (node (ref "U$23") (pin "32") (pinfunction "32:VDD_32") (pintype "bidirectional"))
      (node (ref "U$23") (pin "48") (pinfunction "48:VDD_48") (pintype "bidirectional"))
      (node (ref "U$23") (pin "64") (pinfunction "64:VDD_64") (pintype "bidirectional"))
      (node (ref "U$24") (pin "V3.3") (pinfunction "V3.3_V3.3") (pintype "bidirectional"))
      (node (ref "U$24") (pin "V3.3@1") (pinfunction "V3.3_V3.3@1") (pintype "bidirectional"))
      (node (ref "U$24") (pin "V3.3@2") (pinfunction "V3.3_V3.3@2") (pintype "bidirectional"))
      (node (ref "U1") (pin "23") (pinfunction "VCCB_2_23") (pintype "power_in"))
      (node (ref "U1") (pin "24") (pinfunction "VCCB_24") (pintype "power_in"))
    )
    (net (code "88") (name "/V5") (class "Default")
      (node (ref "C5") (pin "1") (pinfunction "1_1") (pintype "passive"))
      (node (ref "C9") (pin "1") (pinfunction "1_1") (pintype "passive"))
      (node (ref "JP6") (pin "20") (pinfunction "20_20") (pintype "passive"))
      (node (ref "JP6") (pin "21") (pinfunction "21_21") (pintype "passive"))
      (node (ref "JP6") (pin "30") (pinfunction "30_30") (pintype "passive"))
      (node (ref "JP7") (pin "9") (pinfunction "9_9") (pintype "passive"))
      (node (ref "JP8") (pin "9") (pinfunction "9_9") (pintype "passive"))
      (node (ref "SJ11") (pin "2") (pinfunction "2_2") (pintype "passive"))
      (node (ref "U$13") (pin "16") (pinfunction "VCC1_16") (pintype "bidirectional"))
      (node (ref "U$15") (pin "VIN") (pinfunction "VI_VIN") (pintype "input"))
      (node (ref "U$16") (pin "VO") (pinfunction "P$3_VO") (pintype "output"))
      (node (ref "U$24") (pin "V5") (pinfunction "V5_V5") (pintype "bidirectional"))
      (node (ref "U1") (pin "1") (pinfunction "VCCA_1") (pintype "power_in"))
    )
    (net (code "89") (name "/V12") (class "Default")
      (node (ref "C2") (pin "1") (pinfunction "1_1") (pintype "passive"))
      (node (ref "J2") (pin "3") (pinfunction "3_3") (pintype "passive"))
      (node (ref "SJ3") (pin "2") (pinfunction "2_2") (pintype "passive"))
      (node (ref "U$13") (pin "8") (pinfunction "VCC2_8") (pintype "bidirectional"))
      (node (ref "U$16") (pin "VI") (pinfunction "P$1_VI") (pintype "input"))
    )
    (net (code "90") (name "/VADJ") (class "Default")
      (node (ref "C4") (pin "1") (pinfunction "1_1") (pintype "passive"))
      (node (ref "D2") (pin "A") (pinfunction "A_A") (pintype "passive"))
      (node (ref "LM317") (pin "2") (pinfunction "2_2") (pintype "passive"))
      (node (ref "R1") (pin "1") (pinfunction "1_1") (pintype "passive"))
      (node (ref "R2") (pin "2") (pinfunction "S_2") (pintype "passive"))
    )
    (net (code "91") (name "/VBUS") (class "Default")
      (node (ref "JP2") (pin "2") (pinfunction "2_2") (pintype "passive"))
      (node (ref "JP2") (pin "4") (pinfunction "4_4") (pintype "passive"))
      (node (ref "SJ12") (pin "2") (pinfunction "2_2") (pintype "passive"))
    )
    (net (code "92") (name "/VBUS_A") (class "Default")
      (node (ref "JP1") (pin "4") (pinfunction "4_4") (pintype "passive"))
      (node (ref "SJ14") (pin "2") (pinfunction "2_2") (pintype "passive"))
    )
    (net (code "93") (name "/VCAP") (class "Default")
      (node (ref "C12") (pin "1") (pinfunction "1_1") (pintype "passive"))
      (node (ref "U$23") (pin "30") (pinfunction "30:VCAP_30") (pintype "bidirectional"))
    )
    (net (code "94") (name "/VCONN") (class "Default")
      (node (ref "JP2") (pin "6") (pinfunction "6_6") (pintype "passive"))
      (node (ref "SJ13") (pin "2") (pinfunction "2_2") (pintype "passive"))
    )
    (net (code "95") (name "/VCONNA") (class "Default")
      (node (ref "JP1") (pin "1") (pinfunction "1_1") (pintype "passive"))
      (node (ref "SJ9") (pin "1") (pinfunction "1_1") (pintype "passive"))
    )
    (net (code "96") (name "/VDD") (class "Default")
      (node (ref "JP1") (pin "12") (pinfunction "12_12") (pintype "passive"))
      (node (ref "SJ8") (pin "1") (pinfunction "1_1") (pintype "passive"))
    )
    (net (code "97") (name "/VLT_DIR") (class "Default")
      (node (ref "U$23") (pin "36") (pinfunction "PB15_36") (pintype "bidirectional"))
      (node (ref "U1") (pin "2") (pinfunction "DIR_2") (pintype "input"))
    )
    (net (code "98") (name "/VPU") (class "Default")
      (node (ref "JP1") (pin "11") (pinfunction "11_11") (pintype "passive"))
    )
    (net (code "99") (name "/V_PULLUP") (class "Default")
      (node (ref "JP1") (pin "2") (pinfunction "2_2") (pintype "passive"))
    )
    (net (code "100") (name "/WIFI_CS") (class "Default")
      (node (ref "U$23") (pin "28") (pinfunction "PB2_28") (pintype "bidirectional"))
      (node (ref "U$24") (pin "D8") (pinfunction "D8_D8") (pintype "bidirectional"))
    )
    (net (code "101") (name "/WIFI_GPIO") (class "Default")
      (node (ref "U$24") (pin "D1") (pinfunction "D1_D1") (pintype "bidirectional"))
    )
    (net (code "102") (name "/WIFI_IRQ") (class "Default")
      (node (ref "U$23") (pin "29") (pinfunction "PB10_29") (pintype "bidirectional"))
      (node (ref "U$24") (pin "D0") (pinfunction "D0_D0") (pintype "bidirectional"))
    )
    (net (code "103") (name "Net-(R4-Pad1)") (class "Default")
      (node (ref "R4") (pin "1") (pinfunction "1_1") (pintype "passive"))
      (node (ref "R5") (pin "2") (pinfunction "2_2") (pintype "passive"))
      (node (ref "U$18") (pin "E") (pinfunction "E_E") (pintype "bidirectional"))
    )
    (net (code "104") (name "Net-(R6-Pad1)") (class "Default")
      (node (ref "R6") (pin "1") (pinfunction "1_1") (pintype "passive"))
      (node (ref "U$19") (pin "D") (pinfunction "D_D") (pintype "bidirectional"))
    )
    (net (code "105") (name "Net-(R6-Pad2)") (class "Default")
      (node (ref "R6") (pin "2") (pinfunction "2_2") (pintype "passive"))
      (node (ref "U$18") (pin "CATH") (pinfunction "CATH_CATH") (pintype "bidirectional"))
    )
    (net (code "106") (name "Net-(U$2-11)") (class "Default")
      (node (ref "JP6") (pin "15") (pinfunction "15_15") (pintype "passive"))
      (node (ref "U$2") (pin "P$11") (pinfunction "11_P$11") (pintype "passive"))
    )
    (net (code "107") (name "Net-(U$2-22)") (class "Default")
      (node (ref "JP6") (pin "16") (pinfunction "16_16") (pintype "passive"))
      (node (ref "U$2") (pin "P$22") (pinfunction "22_P$22") (pintype "passive"))
    )
    (net (code "108") (name "Net-(U$2-33)") (class "Default")
      (node (ref "JP6") (pin "17") (pinfunction "17_17") (pintype "passive"))
      (node (ref "U$2") (pin "P$33") (pinfunction "33_P$33") (pintype "passive"))
    )
    (net (code "109") (name "Net-(U$2-44)") (class "Default")
      (node (ref "JP6") (pin "18") (pinfunction "18_18") (pintype "passive"))
      (node (ref "U$2") (pin "P$44") (pinfunction "44_P$44") (pintype "passive"))
    )
    (net (code "110") (name "Net-(U$6-11)") (class "Default")
      (node (ref "JP6") (pin "23") (pinfunction "23_23") (pintype "passive"))
      (node (ref "U$6") (pin "P$11") (pinfunction "11_P$11") (pintype "passive"))
    )
    (net (code "111") (name "Net-(U$6-22)") (class "Default")
      (node (ref "JP6") (pin "24") (pinfunction "24_24") (pintype "passive"))
      (node (ref "U$6") (pin "P$22") (pinfunction "22_P$22") (pintype "passive"))
    )
    (net (code "112") (name "Net-(U$6-33)") (class "Default")
      (node (ref "JP6") (pin "26") (pinfunction "26_26") (pintype "passive"))
      (node (ref "U$6") (pin "P$33") (pinfunction "33_P$33") (pintype "passive"))
    )
    (net (code "113") (name "Net-(U$7-11)") (class "Default")
      (node (ref "JP6") (pin "25") (pinfunction "25_25") (pintype "passive"))
      (node (ref "U$7") (pin "P$11") (pinfunction "11_P$11") (pintype "passive"))
    )
    (net (code "114") (name "Net-(U$7-22)") (class "Default")
      (node (ref "JP6") (pin "28") (pinfunction "28_28") (pintype "passive"))
      (node (ref "U$7") (pin "P$22") (pinfunction "22_P$22") (pintype "passive"))
    )
    (net (code "115") (name "Net-(U$7-33)") (class "Default")
      (node (ref "JP6") (pin "27") (pinfunction "27_27") (pintype "passive"))
      (node (ref "U$7") (pin "P$33") (pinfunction "33_P$33") (pintype "passive"))
    )
    (net (code "116") (name "Net-(U$8-11)") (class "Default")
      (node (ref "JP8") (pin "5") (pinfunction "5_5") (pintype "passive"))
      (node (ref "U$8") (pin "P$11") (pinfunction "11_P$11") (pintype "passive"))
    )
    (net (code "117") (name "Net-(U$8-22)") (class "Default")
      (node (ref "JP8") (pin "4") (pinfunction "4_4") (pintype "passive"))
      (node (ref "U$8") (pin "P$22") (pinfunction "22_P$22") (pintype "passive"))
    )
    (net (code "118") (name "Net-(U$8-33)") (class "Default")
      (node (ref "JP8") (pin "3") (pinfunction "3_3") (pintype "passive"))
      (node (ref "U$8") (pin "P$33") (pinfunction "33_P$33") (pintype "passive"))
    )
    (net (code "119") (name "Net-(U$8-44)") (class "Default")
      (node (ref "JP8") (pin "2") (pinfunction "2_2") (pintype "passive"))
      (node (ref "U$8") (pin "P$44") (pinfunction "44_P$44") (pintype "passive"))
    )
    (net (code "120") (name "Net-(U$9-11)") (class "Default")
      (node (ref "JP7") (pin "5") (pinfunction "5_5") (pintype "passive"))
      (node (ref "U$9") (pin "P$11") (pinfunction "11_P$11") (pintype "passive"))
    )
    (net (code "121") (name "Net-(U$9-22)") (class "Default")
      (node (ref "JP7") (pin "4") (pinfunction "4_4") (pintype "passive"))
      (node (ref "U$9") (pin "P$22") (pinfunction "22_P$22") (pintype "passive"))
    )
    (net (code "122") (name "Net-(U$9-33)") (class "Default")
      (node (ref "JP7") (pin "3") (pinfunction "3_3") (pintype "passive"))
      (node (ref "U$9") (pin "P$33") (pinfunction "33_P$33") (pintype "passive"))
    )
    (net (code "123") (name "Net-(U$9-44)") (class "Default")
      (node (ref "JP7") (pin "2") (pinfunction "2_2") (pintype "passive"))
      (node (ref "U$9") (pin "P$44") (pinfunction "44_P$44") (pintype "passive"))
    )
    (net (code "124") (name "Net-(U$10-33)") (class "Default")
      (node (ref "JP7") (pin "7") (pinfunction "7_7") (pintype "passive"))
      (node (ref "U$10") (pin "P$33") (pinfunction "33_P$33") (pintype "passive"))
    )
    (net (code "125") (name "Net-(U$10-44)") (class "Default")
      (node (ref "JP7") (pin "6") (pinfunction "6_6") (pintype "passive"))
      (node (ref "U$10") (pin "P$44") (pinfunction "44_P$44") (pintype "passive"))
    )
    (net (code "126") (name "Net-(U$11-33)") (class "Default")
      (node (ref "JP8") (pin "7") (pinfunction "7_7") (pintype "passive"))
      (node (ref "U$11") (pin "P$33") (pinfunction "33_P$33") (pintype "passive"))
    )
    (net (code "127") (name "Net-(U$11-44)") (class "Default")
      (node (ref "JP8") (pin "6") (pinfunction "6_6") (pintype "passive"))
      (node (ref "U$11") (pin "P$44") (pinfunction "44_P$44") (pintype "passive"))
    )
    (net (code "128") (name "Net-(U$23-PH1)") (class "Default")
      (node (ref "R3") (pin "2") (pinfunction "2_2") (pintype "passive"))
      (node (ref "U$23") (pin "6") (pinfunction "PH1_6") (pintype "bidirectional"))
    )
    (net (code "129") (name "unconnected-(JP1-Pad3)") (class "Default")
      (node (ref "JP1") (pin "3") (pinfunction "3_3") (pintype "passive"))
    )
    (net (code "130") (name "unconnected-(JP6-Pad29)") (class "Default")
      (node (ref "JP6") (pin "29") (pinfunction "29_29") (pintype "passive"))
    )
    (net (code "131") (name "unconnected-(R2-E-Pad3)") (class "Default")
      (node (ref "R2") (pin "3") (pinfunction "E_3") (pintype "passive"))
    )
    (net (code "132") (name "unconnected-(U$4-4-PadP$4)") (class "Default")
      (node (ref "U$4") (pin "P$4") (pinfunction "4_P$4") (pintype "passive"))
    )
    (net (code "133") (name "unconnected-(U$4-44-PadP$44)") (class "Default")
      (node (ref "U$4") (pin "P$44") (pinfunction "44_P$44") (pintype "passive"))
    )
    (net (code "134") (name "unconnected-(U$6-4-PadP$4)") (class "Default")
      (node (ref "U$6") (pin "P$4") (pinfunction "4_P$4") (pintype "passive"))
    )
    (net (code "135") (name "unconnected-(U$6-44-PadP$44)") (class "Default")
      (node (ref "U$6") (pin "P$44") (pinfunction "44_P$44") (pintype "passive"))
    )
    (net (code "136") (name "unconnected-(U$7-4-PadP$4)") (class "Default")
      (node (ref "U$7") (pin "P$4") (pinfunction "4_P$4") (pintype "passive"))
    )
    (net (code "137") (name "unconnected-(U$7-44-PadP$44)") (class "Default")
      (node (ref "U$7") (pin "P$44") (pinfunction "44_P$44") (pintype "passive"))
    )
    (net (code "138") (name "unconnected-(U$10-1-PadP$1)") (class "Default")
      (node (ref "U$10") (pin "P$1") (pinfunction "1_P$1") (pintype "passive"))
    )
    (net (code "139") (name "unconnected-(U$10-2-PadP$2)") (class "Default")
      (node (ref "U$10") (pin "P$2") (pinfunction "2_P$2") (pintype "passive"))
    )
    (net (code "140") (name "unconnected-(U$10-11-PadP$11)") (class "Default")
      (node (ref "U$10") (pin "P$11") (pinfunction "11_P$11") (pintype "passive"))
    )
    (net (code "141") (name "unconnected-(U$10-22-PadP$22)") (class "Default")
      (node (ref "U$10") (pin "P$22") (pinfunction "22_P$22") (pintype "passive"))
    )
    (net (code "142") (name "unconnected-(U$11-1-PadP$1)") (class "Default")
      (node (ref "U$11") (pin "P$1") (pinfunction "1_P$1") (pintype "passive"))
    )
    (net (code "143") (name "unconnected-(U$11-2-PadP$2)") (class "Default")
      (node (ref "U$11") (pin "P$2") (pinfunction "2_P$2") (pintype "passive"))
    )
    (net (code "144") (name "unconnected-(U$11-11-PadP$11)") (class "Default")
      (node (ref "U$11") (pin "P$11") (pinfunction "11_P$11") (pintype "passive"))
    )
    (net (code "145") (name "unconnected-(U$11-22-PadP$22)") (class "Default")
      (node (ref "U$11") (pin "P$22") (pinfunction "22_P$22") (pintype "passive"))
    )
    (net (code "146") (name "unconnected-(U$12-AN-PadANODE)") (class "Default")
      (node (ref "U$12") (pin "ANODE") (pinfunction "AN_ANODE") (pintype "input"))
    )
    (net (code "147") (name "unconnected-(U$12-CA-PadCATHODE)") (class "Default")
      (node (ref "U$12") (pin "CATHODE") (pinfunction "CA_CATHODE") (pintype "output"))
    )
    (net (code "148") (name "unconnected-(U$24-PadA0)") (class "Default")
      (node (ref "U$24") (pin "A0") (pinfunction "A0_A0") (pintype "bidirectional"))
    )
    (net (code "149") (name "unconnected-(U$24-PadCLK)") (class "Default")
      (node (ref "U$24") (pin "CLK") (pinfunction "CLK_CLK") (pintype "bidirectional"))
    )
    (net (code "150") (name "unconnected-(U$24-PadCMD)") (class "Default")
      (node (ref "U$24") (pin "CMD") (pinfunction "CMD_CMD") (pintype "bidirectional"))
    )
    (net (code "151") (name "unconnected-(U$24-PadD2)") (class "Default")
      (node (ref "U$24") (pin "D2") (pinfunction "D2_D2") (pintype "bidirectional"))
    )
    (net (code "152") (name "unconnected-(U$24-PadD3)") (class "Default")
      (node (ref "U$24") (pin "D3") (pinfunction "D3_D3") (pintype "bidirectional"))
    )
    (net (code "153") (name "unconnected-(U$24-PadD4)") (class "Default")
      (node (ref "U$24") (pin "D4") (pinfunction "D4_D4") (pintype "bidirectional"))
    )
    (net (code "154") (name "unconnected-(U$24-PadEN)") (class "Default")
      (node (ref "U$24") (pin "EN") (pinfunction "EN_EN") (pintype "bidirectional"))
    )
    (net (code "155") (name "unconnected-(U$24-PadRST)") (class "Default")
      (node (ref "U$24") (pin "RST") (pinfunction "RST_RST") (pintype "bidirectional"))
    )
    (net (code "156") (name "unconnected-(U$24-PadRSV)") (class "Default")
      (node (ref "U$24") (pin "RSV") (pinfunction "RSV_RSV") (pintype "bidirectional"))
    )
    (net (code "157") (name "unconnected-(U$24-PadRX)") (class "Default")
      (node (ref "U$24") (pin "RX") (pinfunction "RX_RX") (pintype "bidirectional"))
    )
    (net (code "158") (name "unconnected-(U$24-PadSD0)") (class "Default")
      (node (ref "U$24") (pin "SD0") (pinfunction "SD0_SD0") (pintype "bidirectional"))
    )
    (net (code "159") (name "unconnected-(U$24-PadSD1)") (class "Default")
      (node (ref "U$24") (pin "SD1") (pinfunction "SD1_SD1") (pintype "bidirectional"))
    )
    (net (code "160") (name "unconnected-(U$24-PadSD2)") (class "Default")
      (node (ref "U$24") (pin "SD2") (pinfunction "SD2_SD2") (pintype "bidirectional"))
    )
    (net (code "161") (name "unconnected-(U$24-PadSD3)") (class "Default")
      (node (ref "U$24") (pin "SD3") (pinfunction "SD3_SD3") (pintype "bidirectional"))
    )
    (net (code "162") (name "unconnected-(U$24-PadTX)") (class "Default")
      (node (ref "U$24") (pin "TX") (pinfunction "TX_TX") (pintype "bidirectional"))
    )
    (net (code "163") (name "unconnected-(U$24-RSV-PadRSV@1)") (class "Default")
      (node (ref "U$24") (pin "RSV@1") (pinfunction "RSV_RSV@1") (pintype "bidirectional"))
    )
    (net (code "164") (name "unconnected-(U1-A6-Pad9)") (class "Default")
      (node (ref "U1") (pin "9") (pinfunction "A6_9") (pintype "bidirectional"))
    )
    (net (code "165") (name "unconnected-(U1-A7-Pad10)") (class "Default")
      (node (ref "U1") (pin "10") (pinfunction "A7_10") (pintype "bidirectional"))
    )
    (net (code "166") (name "unconnected-(U1-B6-Pad15)") (class "Default")
      (node (ref "U1") (pin "15") (pinfunction "B6_15") (pintype "bidirectional"))
    )
    (net (code "167") (name "unconnected-(U1-B7-Pad14)") (class "Default")
      (node (ref "U1") (pin "14") (pinfunction "B7_14") (pintype "bidirectional"))
    )
  )
)
